# SmartLURE.net
KiCad netlist of a schematic drawn in EAGLE
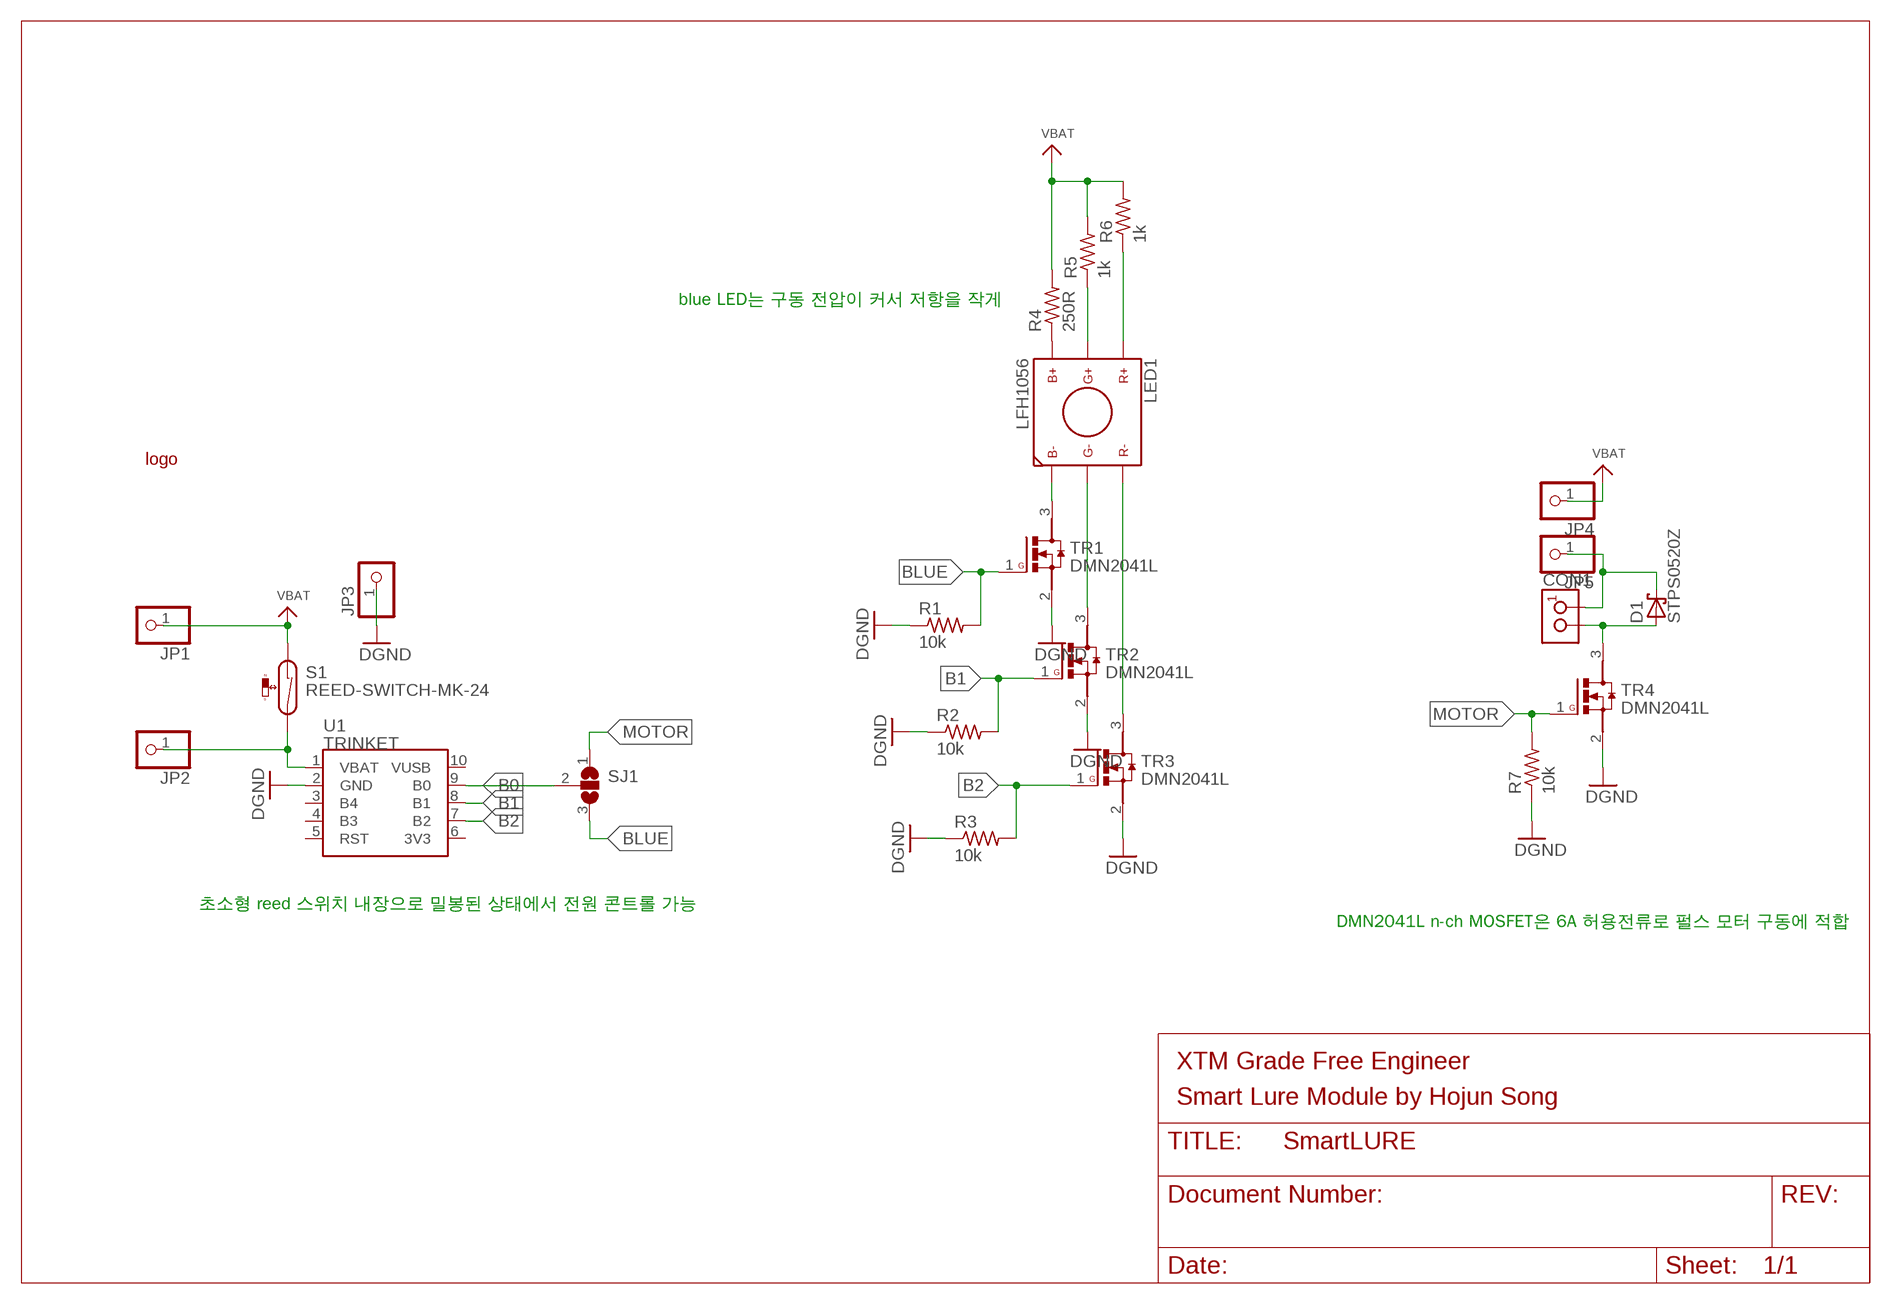
[diagram p0: schematic, sheet 1]

(export (version "E")
  (design (tool "Eeschema 10.0.6"))
  (components
    (comp (ref "CON1")
      (value "PINHEADER_1.27")
      (footprint "eagle-import:PINHEADER_1.27")
      (libsource (lib "eagle-import") (part "PINHEADER_1.27"))
    )
    (comp (ref "D1")
      (value "STPS0520Z")
      (footprint "eagle-import:SOD-123")
      (libsource (lib "eagle-import") (part "STPS0520Z"))
    )
    (comp (ref "JP1")
      (value "PINHD-1X1CB")
      (footprint "eagle-import:1X01-CLEANBIG")
      (libsource (lib "eagle-import") (part "PINHD-1X1CB"))
    )
    (comp (ref "JP2")
      (value "PINHD-1X1CB")
      (footprint "eagle-import:1X01-CLEANBIG")
      (libsource (lib "eagle-import") (part "PINHD-1X1CB"))
    )
    (comp (ref "JP3")
      (value "PINHD-1X1CB")
      (footprint "eagle-import:1X01-CLEANBIG")
      (libsource (lib "eagle-import") (part "PINHD-1X1CB"))
    )
    (comp (ref "JP4")
      (value "PINHD-1X1CB")
      (footprint "eagle-import:1X01-CLEANBIG")
      (libsource (lib "eagle-import") (part "PINHD-1X1CB"))
    )
    (comp (ref "JP5")
      (value "PINHD-1X1CB")
      (footprint "eagle-import:1X01-CLEANBIG")
      (libsource (lib "eagle-import") (part "PINHD-1X1CB"))
    )
    (comp (ref "LED1")
      (value "LFH1056")
      (footprint "eagle-import:LFH1056")
      (libsource (lib "eagle-import") (part "LFH1056"))
    )
    (comp (ref "LOGO1")
      (value "GRADEFREELOGO-10")
      (footprint "eagle-import:GRADEFREELOGO-10")
      (libsource (lib "eagle-import") (part "GRADEFREELOGO-10"))
    )
    (comp (ref "R1")
      (value "10k")
      (footprint "eagle-import:R0603(1608)")
      (libsource (lib "eagle-import") (part "R0603(1608)"))
    )
    (comp (ref "R2")
      (value "10k")
      (footprint "eagle-import:R0603(1608)")
      (libsource (lib "eagle-import") (part "R0603(1608)"))
    )
    (comp (ref "R3")
      (value "10k")
      (footprint "eagle-import:R0603(1608)")
      (libsource (lib "eagle-import") (part "R0603(1608)"))
    )
    (comp (ref "R4")
      (value "250R")
      (footprint "eagle-import:R0603(1608)")
      (libsource (lib "eagle-import") (part "R0603(1608)"))
    )
    (comp (ref "R5")
      (value "1k")
      (footprint "eagle-import:R0603(1608)")
      (libsource (lib "eagle-import") (part "R0603(1608)"))
    )
    (comp (ref "R6")
      (value "1k")
      (footprint "eagle-import:R0603(1608)")
      (libsource (lib "eagle-import") (part "R0603(1608)"))
    )
    (comp (ref "R7")
      (value "10k")
      (footprint "eagle-import:R0603(1608)")
      (libsource (lib "eagle-import") (part "R0603(1608)"))
    )
    (comp (ref "S1")
      (value "REED-SWITCH-MK-24")
      (footprint "eagle-import:MK24")
      (libsource (lib "eagle-import") (part "REED-SWITCH-MK-24"))
    )
    (comp (ref "SJ1")
      (value "SJ2W")
      (footprint "eagle-import:SJ_2")
      (libsource (lib "eagle-import") (part "SJ2W"))
    )
    (comp (ref "TR1")
      (value "DMN2041L")
      (footprint "eagle-import:SOT23")
      (libsource (lib "eagle-import") (part "DMN2041L"))
    )
    (comp (ref "TR2")
      (value "DMN2041L")
      (footprint "eagle-import:SOT23")
      (libsource (lib "eagle-import") (part "DMN2041L"))
    )
    (comp (ref "TR3")
      (value "DMN2041L")
      (footprint "eagle-import:SOT23")
      (libsource (lib "eagle-import") (part "DMN2041L"))
    )
    (comp (ref "TR4")
      (value "DMN2041L")
      (footprint "eagle-import:SOT23")
      (libsource (lib "eagle-import") (part "DMN2041L"))
    )
    (comp (ref "U1")
      (value "TRINKET")
      (footprint "eagle-import:TRINKET")
      (libsource (lib "eagle-import") (part "TRINKET"))
    )
  )
  (nets
    (net (code "1") (name "B0") (class "Default")
      (node (ref "SJ1") (pin "2") (pinfunction "2_2") (pintype "passive"))
      (node (ref "U1") (pin "9") (pinfunction "B0_9") (pintype "bidirectional"))
    )
    (net (code "2") (name "B1") (class "Default")
      (node (ref "R2") (pin "2") (pinfunction "2_2") (pintype "passive"))
      (node (ref "TR2") (pin "1") (pinfunction "G_1") (pintype "bidirectional"))
      (node (ref "U1") (pin "8") (pinfunction "B1_8") (pintype "bidirectional"))
    )
    (net (code "3") (name "B2") (class "Default")
      (node (ref "R3") (pin "2") (pinfunction "2_2") (pintype "passive"))
      (node (ref "TR3") (pin "1") (pinfunction "G_1") (pintype "bidirectional"))
      (node (ref "U1") (pin "7") (pinfunction "B2_7") (pintype "bidirectional"))
    )
    (net (code "4") (name "BLUE") (class "Default")
      (node (ref "R1") (pin "2") (pinfunction "2_2") (pintype "passive"))
      (node (ref "SJ1") (pin "3") (pinfunction "3_3") (pintype "passive"))
      (node (ref "TR1") (pin "1") (pinfunction "G_1") (pintype "bidirectional"))
    )
    (net (code "5") (name "DGND") (class "Default")
      (node (ref "JP3") (pin "1") (pinfunction "1_1") (pintype "passive"))
      (node (ref "R1") (pin "1") (pinfunction "1_1") (pintype "passive"))
      (node (ref "R2") (pin "1") (pinfunction "1_1") (pintype "passive"))
      (node (ref "R3") (pin "1") (pinfunction "1_1") (pintype "passive"))
      (node (ref "R7") (pin "1") (pinfunction "1_1") (pintype "passive"))
      (node (ref "TR1") (pin "2") (pinfunction "S_2") (pintype "bidirectional"))
      (node (ref "TR2") (pin "2") (pinfunction "S_2") (pintype "bidirectional"))
      (node (ref "TR3") (pin "2") (pinfunction "S_2") (pintype "bidirectional"))
      (node (ref "TR4") (pin "2") (pinfunction "S_2") (pintype "bidirectional"))
      (node (ref "U1") (pin "2") (pinfunction "GND_2") (pintype "bidirectional"))
    )
    (net (code "6") (name "MOTOR") (class "Default")
      (node (ref "R7") (pin "2") (pinfunction "2_2") (pintype "passive"))
      (node (ref "SJ1") (pin "1") (pinfunction "1_1") (pintype "passive"))
      (node (ref "TR4") (pin "1") (pinfunction "G_1") (pintype "bidirectional"))
    )
    (net (code "7") (name "Net-(CON1-1)") (class "Default")
      (node (ref "CON1") (pin "P$1") (pinfunction "1_P$1") (pintype "passive"))
      (node (ref "D1") (pin "C") (pinfunction "C_C") (pintype "passive"))
      (node (ref "JP5") (pin "1") (pinfunction "1_1") (pintype "passive"))
    )
    (net (code "8") (name "Net-(CON1-2)") (class "Default")
      (node (ref "CON1") (pin "P$2") (pinfunction "2_P$2") (pintype "passive"))
      (node (ref "D1") (pin "A") (pinfunction "A_A") (pintype "passive"))
      (node (ref "TR4") (pin "3") (pinfunction "D_3") (pintype "bidirectional"))
    )
    (net (code "9") (name "Net-(LED1-PadB+)") (class "Default")
      (node (ref "LED1") (pin "B+") (pinfunction "B+_B+") (pintype "input"))
      (node (ref "R4") (pin "1") (pinfunction "1_1") (pintype "passive"))
    )
    (net (code "10") (name "Net-(LED1-PadG+)") (class "Default")
      (node (ref "LED1") (pin "G+") (pinfunction "G+_G+") (pintype "input"))
      (node (ref "R5") (pin "1") (pinfunction "1_1") (pintype "passive"))
    )
    (net (code "11") (name "Net-(LED1-PadR+)") (class "Default")
      (node (ref "LED1") (pin "R+") (pinfunction "R+_R+") (pintype "input"))
      (node (ref "R6") (pin "1") (pinfunction "1_1") (pintype "passive"))
    )
    (net (code "12") (name "Net-(TR1-D)") (class "Default")
      (node (ref "LED1") (pin "B-") (pinfunction "B-_B-") (pintype "input"))
      (node (ref "TR1") (pin "3") (pinfunction "D_3") (pintype "bidirectional"))
    )
    (net (code "13") (name "Net-(TR2-D)") (class "Default")
      (node (ref "LED1") (pin "G-") (pinfunction "G-_G-") (pintype "input"))
      (node (ref "TR2") (pin "3") (pinfunction "D_3") (pintype "bidirectional"))
    )
    (net (code "14") (name "Net-(TR3-D)") (class "Default")
      (node (ref "LED1") (pin "R-") (pinfunction "R-_R-") (pintype "input"))
      (node (ref "TR3") (pin "3") (pinfunction "D_3") (pintype "bidirectional"))
    )
    (net (code "15") (name "Net-(U1-VBAT)") (class "Default")
      (node (ref "JP2") (pin "1") (pinfunction "1_1") (pintype "passive"))
      (node (ref "S1") (pin "2") (pinfunction "2_2") (pintype "passive"))
      (node (ref "U1") (pin "1") (pinfunction "VBAT_1") (pintype "bidirectional"))
    )
    (net (code "16") (name "VBAT") (class "Default")
      (node (ref "JP1") (pin "1") (pinfunction "1_1") (pintype "passive"))
      (node (ref "JP4") (pin "1") (pinfunction "1_1") (pintype "passive"))
      (node (ref "R4") (pin "2") (pinfunction "2_2") (pintype "passive"))
      (node (ref "R5") (pin "2") (pinfunction "2_2") (pintype "passive"))
      (node (ref "R6") (pin "2") (pinfunction "2_2") (pintype "passive"))
      (node (ref "S1") (pin "1") (pinfunction "1_1") (pintype "passive"))
    )
    (net (code "17") (name "unconnected-(U1-3V3-Pad6)") (class "Default")
      (node (ref "U1") (pin "6") (pinfunction "3V3_6") (pintype "bidirectional"))
    )
    (net (code "18") (name "unconnected-(U1-B3-Pad4)") (class "Default")
      (node (ref "U1") (pin "4") (pinfunction "B3_4") (pintype "bidirectional"))
    )
    (net (code "19") (name "unconnected-(U1-B4-Pad3)") (class "Default")
      (node (ref "U1") (pin "3") (pinfunction "B4_3") (pintype "bidirectional"))
    )
    (net (code "20") (name "unconnected-(U1-RST-Pad5)") (class "Default")
      (node (ref "U1") (pin "5") (pinfunction "RST_5") (pintype "bidirectional"))
    )
    (net (code "21") (name "unconnected-(U1-VUSB-Pad10)") (class "Default")
      (node (ref "U1") (pin "10") (pinfunction "VUSB_10") (pintype "bidirectional"))
    )
  )
)
